# Inputs.net
KiCad netlist of a schematic drawn in Altium Designer
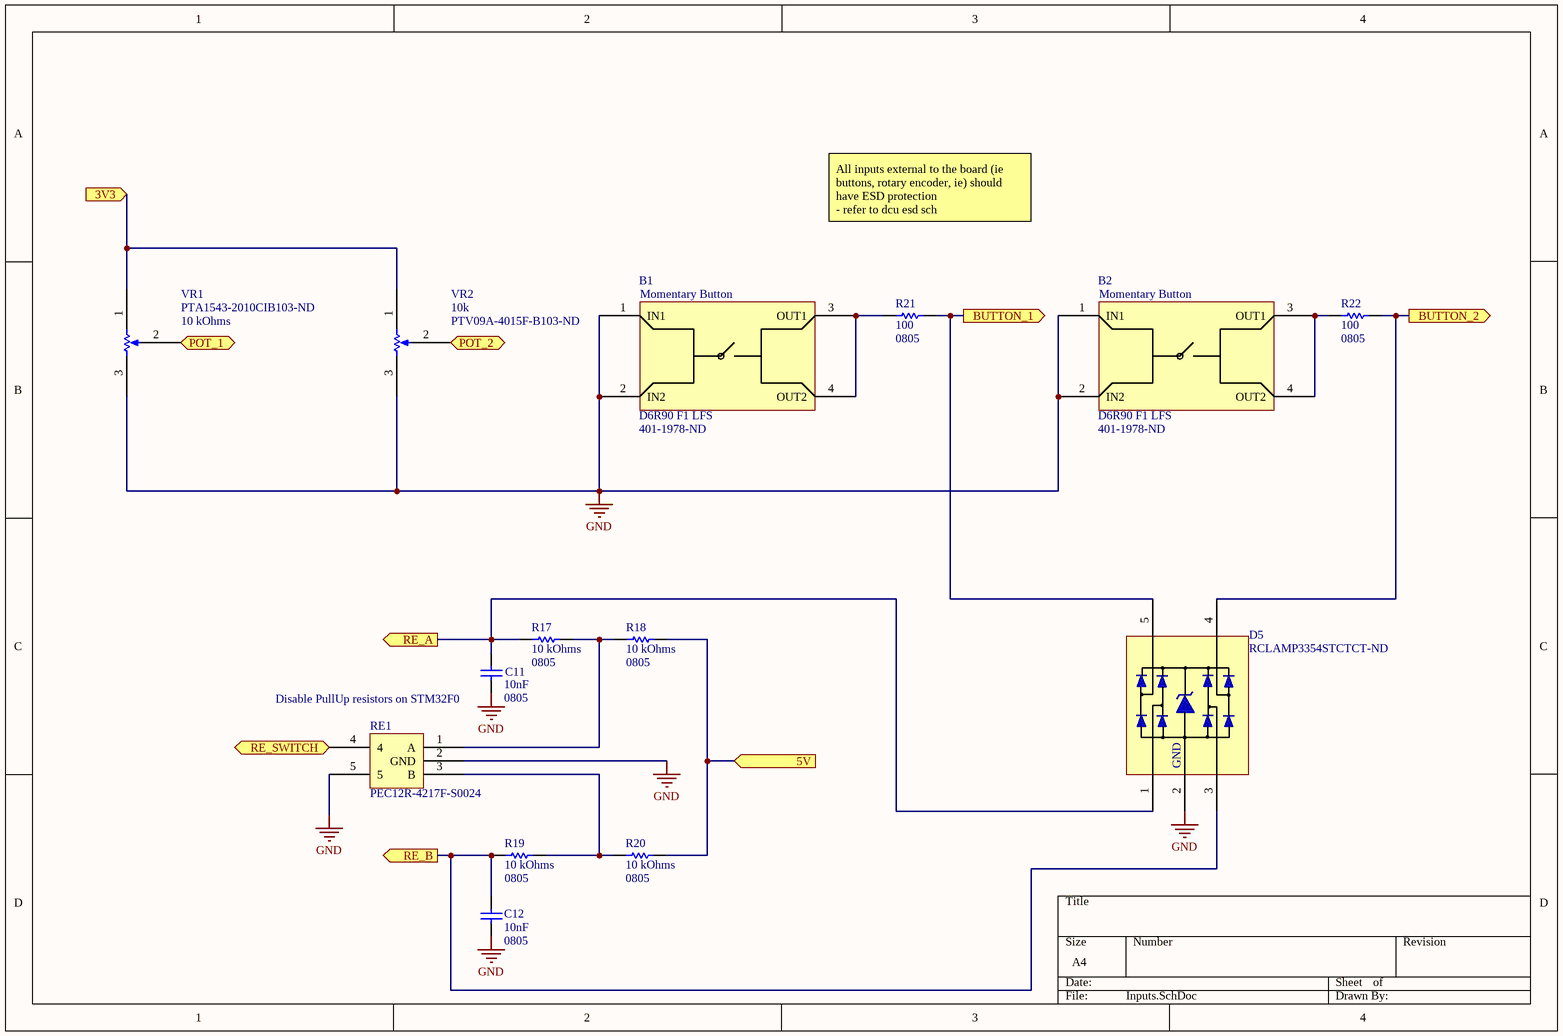
[diagram p0: Inputs.SchDoc]

(export (version "E")
  (design (tool "Eeschema 10.0.6"))
  (components
    (comp (ref "B1")
      (value "D6R90 F1 LFS")
      (footprint "MomentaryButton")
      (description "SWITCH PUSH SPST-NO 0.1A 32V")
      (fields (field (name "SUPPLIER PART NUMBER 1") "401-1978-ND"))
      (libsource (lib "Mechanical_Devices") (part "D6R90 F1 LFS"))
    )
    (comp (ref "B2")
      (value "D6R90 F1 LFS")
      (footprint "MomentaryButton")
      (description "SWITCH PUSH SPST-NO 0.1A 32V")
      (fields (field (name "SUPPLIER PART NUMBER 1") "401-1978-ND"))
      (libsource (lib "Mechanical_Devices") (part "D6R90 F1 LFS"))
    )
    (comp (ref "C11")
      (value "CGA4C2C0G1H103J060AA")
      (footprint "CAP0805")
      (description "CAP CER 10000PF 50V C0G 0805")
      (fields
        (field (name "TOLERANCE") "±5%")
        (field (name "CAPACITANCE") "10nF")
        (field (name "PACKAGE / CASE") "0805")
      )
      (libsource (lib "Capacitors") (part "CGA4C2C0G1H103J060AA"))
    )
    (comp (ref "C12")
      (value "CGA4C2C0G1H103J060AA")
      (footprint "CAP0805")
      (description "CAP CER 10000PF 50V C0G 0805")
      (fields
        (field (name "TOLERANCE") "±5%")
        (field (name "CAPACITANCE") "10nF")
        (field (name "PACKAGE / CASE") "0805")
      )
      (libsource (lib "Capacitors") (part "CGA4C2C0G1H103J060AA"))
    )
    (comp (ref "D5")
      (value "RCLAMP3354S.TCT")
      (footprint "SOT95P280X145-5N")
      (description "TVS DIODE 3.3VWM 16VC")
      (fields (field (name "SUPPLIER PART NUMBER 1") "RCLAMP3354STCTCT-ND"))
      (libsource (lib "Diodes") (part "RCLAMP3354S.TCT"))
    )
    (comp (ref "R17")
      (value "RC0805FR-0710KL")
      (footprint "RES0805")
      (description "RES SMD 10K OHM 1% 1/8W 0805")
      (fields
        (field (name "MANUFACTURER") "Yageo")
        (field (name "TOLERANCE") "±1%")
        (field (name "RESISTANCE") "10 kOhms")
        (field (name "PACKAGE / CASE") "0805")
      )
      (libsource (lib "Resistors") (part "RC0805FR-0710KL"))
    )
    (comp (ref "R18")
      (value "RC0805FR-0710KL")
      (footprint "RES0805")
      (description "RES SMD 10K OHM 1% 1/8W 0805")
      (fields
        (field (name "MANUFACTURER") "Yageo")
        (field (name "TOLERANCE") "±1%")
        (field (name "RESISTANCE") "10 kOhms")
        (field (name "PACKAGE / CASE") "0805")
      )
      (libsource (lib "Resistors") (part "RC0805FR-0710KL"))
    )
    (comp (ref "R19")
      (value "RC0805FR-0710KL")
      (footprint "RES0805")
      (description "RES SMD 10K OHM 1% 1/8W 0805")
      (fields
        (field (name "MANUFACTURER") "Yageo")
        (field (name "TOLERANCE") "±1%")
        (field (name "RESISTANCE") "10 kOhms")
        (field (name "PACKAGE / CASE") "0805")
      )
      (libsource (lib "Resistors") (part "RC0805FR-0710KL"))
    )
    (comp (ref "R20")
      (value "RC0805FR-0710KL")
      (footprint "RES0805")
      (description "RES SMD 10K OHM 1% 1/8W 0805")
      (fields
        (field (name "MANUFACTURER") "Yageo")
        (field (name "TOLERANCE") "±1%")
        (field (name "RESISTANCE") "10 kOhms")
        (field (name "PACKAGE / CASE") "0805")
      )
      (libsource (lib "Resistors") (part "RC0805FR-0710KL"))
    )
    (comp (ref "R21")
      (value "RC0805FR-07100RL")
      (footprint "RES0805")
      (description "RES SMD 100 OHM 1% 1/8W 0805")
      (fields
        (field (name "TOLERANCE") "±1%")
        (field (name "RESISTANCE (OHMS)") "100")
        (field (name "PACKAGE / CASE") "0805")
      )
      (libsource (lib "Resistors") (part "RC0805FR-07100RL"))
    )
    (comp (ref "R22")
      (value "RC0805FR-07100RL")
      (footprint "RES0805")
      (description "RES SMD 100 OHM 1% 1/8W 0805")
      (fields
        (field (name "TOLERANCE") "±1%")
        (field (name "RESISTANCE (OHMS)") "100")
        (field (name "PACKAGE / CASE") "0805")
      )
      (libsource (lib "Resistors") (part "RC0805FR-07100RL"))
    )
    (comp (ref "RE1")
      (value "PEC12R-4217F-S0024")
      (footprint "Bourns Inc. PEC12R-4217F-S0024")
      (description "ENCODER ROTARY")
      (libsource (lib "Mechanical_Devices") (part "PEC12R-4217F-S0024"))
    )
    (comp (ref "VR1")
      (value "PTA1543-2010CIB103")
      (footprint "PTA1543-2010CIB103")
      (description "POT SLIDE 10K OHM .05W 15MM")
      (fields
        (field (name "TOLERANCE") "±20%")
        (field (name "SUPPLIER PART NUMBER 1") "PTA1543-2010CIB103-ND")
        (field (name "RESISTANCE") "10 kOhms")
      )
      (libsource (lib "Mechanical_Devices") (part "PTA1543-2010CIB103"))
    )
    (comp (ref "VR2")
      (value "PTV09A-4015F-B103")
      (footprint "PTV09A-4015F-B103")
      (description "POT 10K OHM 1/20W CARBON LINEAR")
      (fields
        (field (name "TOLERANCE") "±20%")
        (field (name "RESISTANCE (OHMS)") "10k")
        (field (name "SUPPLIER PART NUMBER 1") "PTV09A-4015F-B103-ND")
      )
      (libsource (lib "Mechanical_Devices") (part "PTV09A-4015F-B103"))
    )
  )
  (nets
    (net (code "1") (name "/3V3") (class "Default")
      (node (ref "VR1") (pin "1") (pinfunction "1_1") (pintype "passive"))
      (node (ref "VR2") (pin "1") (pinfunction "1_1") (pintype "passive"))
    )
    (net (code "2") (name "/5V") (class "Default")
      (node (ref "R18") (pin "1") (pinfunction "1_1") (pintype "passive"))
      (node (ref "R20") (pin "2") (pinfunction "2_2") (pintype "passive"))
    )
    (net (code "3") (name "/BUTTON_1") (class "Default")
      (node (ref "D5") (pin "5") (pinfunction "5_5") (pintype "passive"))
      (node (ref "R21") (pin "2") (pinfunction "2_2") (pintype "passive"))
    )
    (net (code "4") (name "/BUTTON_2") (class "Default")
      (node (ref "D5") (pin "4") (pinfunction "4_4") (pintype "passive"))
      (node (ref "R22") (pin "2") (pinfunction "2_2") (pintype "passive"))
    )
    (net (code "5") (name "/POT_1") (class "Default")
      (node (ref "VR1") (pin "2") (pinfunction "3_2") (pintype "passive"))
    )
    (net (code "6") (name "/POT_2") (class "Default") (node (ref "VR2") (pin "2") (pintype "passive")))
    (net (code "7") (name "/RE_A") (class "Default")
      (node (ref "C11") (pin "1") (pinfunction "1_1") (pintype "passive"))
      (node (ref "D5") (pin "1") (pinfunction "1_1") (pintype "passive"))
      (node (ref "R17") (pin "2") (pinfunction "2_2") (pintype "passive"))
    )
    (net (code "8") (name "/RE_B") (class "Default")
      (node (ref "C12") (pin "2") (pinfunction "2_2") (pintype "passive"))
      (node (ref "D5") (pin "3") (pinfunction "3_3") (pintype "passive"))
      (node (ref "R19") (pin "2") (pinfunction "2_2") (pintype "passive"))
    )
    (net (code "9") (name "/RE_SWITCH") (class "Default")
      (node (ref "RE1") (pin "4") (pinfunction "4_4") (pintype "passive"))
    )
    (net (code "10") (name "GND") (class "Default")
      (node (ref "B1") (pin "1") (pinfunction "IN1_1") (pintype "passive"))
      (node (ref "B1") (pin "2") (pinfunction "IN2_2") (pintype "passive"))
      (node (ref "B2") (pin "1") (pinfunction "IN1_1") (pintype "passive"))
      (node (ref "B2") (pin "2") (pinfunction "IN2_2") (pintype "passive"))
      (node (ref "C11") (pin "2") (pinfunction "2_2") (pintype "passive"))
      (node (ref "C12") (pin "1") (pinfunction "1_1") (pintype "passive"))
      (node (ref "D5") (pin "2") (pinfunction "GND_2") (pintype "passive"))
      (node (ref "RE1") (pin "2") (pinfunction "GND_2") (pintype "passive"))
      (node (ref "RE1") (pin "5") (pinfunction "5_5") (pintype "passive"))
      (node (ref "VR1") (pin "3") (pinfunction "2_3") (pintype "passive"))
      (node (ref "VR2") (pin "3") (pinfunction "2_3") (pintype "passive"))
    )
    (net (code "11") (name "Net-(B1-OUT1)") (class "Default")
      (node (ref "B1") (pin "3") (pinfunction "OUT1_3") (pintype "passive"))
      (node (ref "B1") (pin "4") (pinfunction "OUT2_4") (pintype "passive"))
      (node (ref "R21") (pin "1") (pinfunction "1_1") (pintype "passive"))
    )
    (net (code "12") (name "Net-(B2-OUT1)") (class "Default")
      (node (ref "B2") (pin "3") (pinfunction "OUT1_3") (pintype "passive"))
      (node (ref "B2") (pin "4") (pinfunction "OUT2_4") (pintype "passive"))
      (node (ref "R22") (pin "1") (pinfunction "1_1") (pintype "passive"))
    )
    (net (code "13") (name "Net-(RE1-A)") (class "Default")
      (node (ref "R17") (pin "1") (pinfunction "1_1") (pintype "passive"))
      (node (ref "R18") (pin "2") (pinfunction "2_2") (pintype "passive"))
      (node (ref "RE1") (pin "1") (pinfunction "A_1") (pintype "passive"))
    )
    (net (code "14") (name "Net-(RE1-B)") (class "Default")
      (node (ref "R19") (pin "1") (pinfunction "1_1") (pintype "passive"))
      (node (ref "R20") (pin "1") (pinfunction "1_1") (pintype "passive"))
      (node (ref "RE1") (pin "3") (pinfunction "B_3") (pintype "passive"))
    )
  )
)
